# 8_ADC_chip.net
KiCad netlist of a schematic drawn in Altium Designer
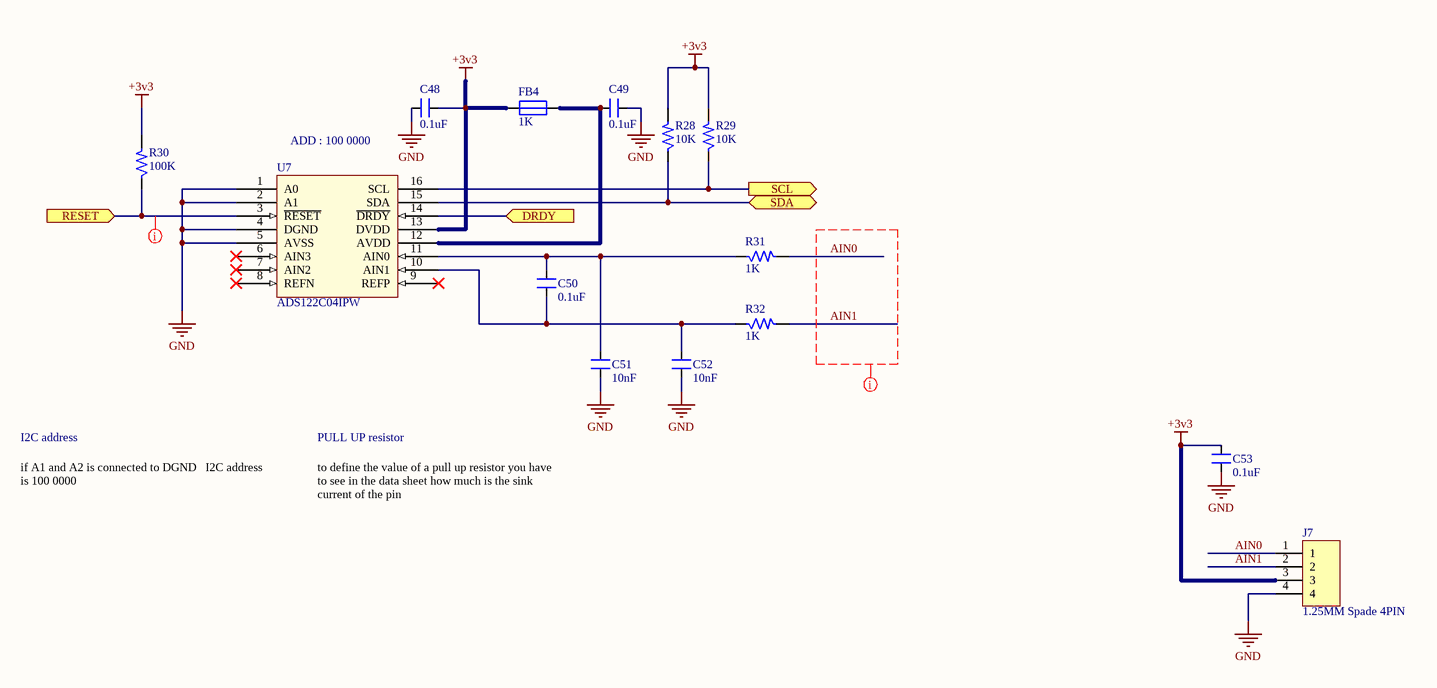
[diagram p0: [8]ADC_chip.SchDoc]

(export (version "E")
  (design (tool "Eeschema 10.0.6"))
  (components
    (comp (ref "C48")
      (value "0.1uF")
      (footprint "CAP_0805")
      (description "0.1µF ±5% 50V Ceramic Capacitor X7R 0805 (2012 Metric)")
      (fields
        (field (name "MANUFACTURER") "AVX Corporation")
        (field (name "MANUFACTURER PART NUMBER") "08055C104JAT4A")
      )
      (libsource (lib "ESTEEMPCBLIB") (part "CAP_0.1uF-50V-5%-0805"))
    )
    (comp (ref "C49")
      (value "0.1uF")
      (footprint "CAP_0805")
      (description "0.1µF ±5% 50V Ceramic Capacitor X7R 0805 (2012 Metric)")
      (fields
        (field (name "MANUFACTURER") "AVX Corporation")
        (field (name "MANUFACTURER PART NUMBER") "08055C104JAT4A")
      )
      (libsource (lib "ESTEEMPCBLIB") (part "CAP_0.1uF-50V-5%-0805"))
    )
    (comp (ref "C50")
      (value "0.1uF")
      (footprint "CAP_0805")
      (description "0.1µF ±5% 50V Ceramic Capacitor X7R 0805 (2012 Metric)")
      (fields
        (field (name "MANUFACTURER") "AVX Corporation")
        (field (name "MANUFACTURER PART NUMBER") "08055C104JAT4A")
      )
      (libsource (lib "ESTEEMPCBLIB") (part "CAP_0.1uF-50V-5%-0805"))
    )
    (comp (ref "C51")
      (value "10nF")
      (footprint "CAP_0805")
      (description "10000pF ±10% 50V Ceramic Capacitor X7R 0805 (2012 Metric)")
      (fields
        (field (name "MANUFACTURER") "Samsung")
        (field (name "MANUFACTURER PART NUMBER") "C0805C103K5RECAUTO")
      )
      (libsource (lib "ESTEEMPCBLIB") (part "CAP_10nF-50V-10%-0805"))
    )
    (comp (ref "C52")
      (value "10nF")
      (footprint "CAP_0805")
      (description "10000pF ±10% 50V Ceramic Capacitor X7R 0805 (2012 Metric)")
      (fields
        (field (name "MANUFACTURER") "Samsung")
        (field (name "MANUFACTURER PART NUMBER") "C0805C103K5RECAUTO")
      )
      (libsource (lib "ESTEEMPCBLIB") (part "CAP_10nF-50V-10%-0805"))
    )
    (comp (ref "C53")
      (value "0.1uF")
      (footprint "CAP_0805")
      (description "0.1µF ±5% 50V Ceramic Capacitor X7R 0805 (2012 Metric)")
      (fields
        (field (name "MANUFACTURER") "AVX Corporation")
        (field (name "MANUFACTURER PART NUMBER") "08055C104JAT4A")
      )
      (libsource (lib "ESTEEMPCBLIB") (part "CAP_0.1uF-50V-5%-0805"))
    )
    (comp (ref "FB4")
      (value "1K")
      (footprint "IND_0805")
      (description "1 kOhms @ 100MHz 1 Power Line Ferrite Bead 0805 (2012 Metric) 1.6A")
      (fields
        (field (name "MANUFACTURER") "Laird")
        (field (name "MANUFACTURER PART NUMBER") "BLM21SP102SH1D")
      )
      (libsource (lib "ESTEEMPCBLIB") (part "FB_1K-100MHZ-1.6A-0805"))
    )
    (comp (ref "J7")
      (value "1.25MM Spade 4PIN")
      (footprint "CON4_50_653004117322_TH_RA")
      (description "4 Pins, 1 Row 1.25mm Pitch, right angle Connector, male")
      (fields (field (name "MANUFACTURER PART NUMBER") "653004117322") (field (name "MANUFACTURER") "JST"))
      (libsource (lib "ESTEEMPCBLIB") (part "CON-PLG_4X1-50-RA-TH"))
    )
    (comp (ref "R28")
      (value "10K")
      (footprint "RES_0603")
      (description "10 kOhms ±1% 0.1W, 1/10W Chip Resistor 0603 (1608 Metric) Automotive AEC-Q200 Thick Film")
      (fields (field (name "MANUFACTURER") "Walsin") (field (name "MANUFACTURER PART NUMBER") "WR06X1002FTL"))
      (libsource (lib "ESTEEMPCBLIB") (part "RES_10K-0.1W-1%-0603"))
    )
    (comp (ref "R29")
      (value "10K")
      (footprint "RES_0603")
      (description "10 kOhms ±1% 0.1W, 1/10W Chip Resistor 0603 (1608 Metric) Automotive AEC-Q200 Thick Film")
      (fields (field (name "MANUFACTURER") "Walsin") (field (name "MANUFACTURER PART NUMBER") "WR06X1002FTL"))
      (libsource (lib "ESTEEMPCBLIB") (part "RES_10K-0.1W-1%-0603"))
    )
    (comp (ref "R30")
      (value "100K")
      (footprint "RES_0603")
      (description "100 kOhms ±1% 0.1W, 1/10W Chip Resistor 0603 (1608 Metric) Automotive AEC-Q200 Thick Film")
      (fields
        (field (name "MANUFACTURER") "Stackpole Electronics")
        (field (name "MANUFACTURER PART NUMBER") "RMCF0603FT100K")
      )
      (libsource (lib "ESTEEMPCBLIB") (part "RES_100K-0.1W-1%-0603"))
    )
    (comp (ref "R31")
      (value "1K")
      (footprint "RES_0603")
      (description "1 kOhms ±1% 0.1W, 1/10W Chip Resistor 0603 (1608 Metric) Automotive AEC-Q200 Thick Film")
      (fields (field (name "MANUFACTURER") "Walsin") (field (name "MANUFACTURER PART NUMBER") "WR06X1001FTL"))
      (libsource (lib "ESTEEMPCBLIB") (part "RES_1K-0.1W-1%-0603"))
    )
    (comp (ref "R32")
      (value "1K")
      (footprint "RES_0603")
      (description "1 kOhms ±1% 0.1W, 1/10W Chip Resistor 0603 (1608 Metric) Automotive AEC-Q200 Thick Film")
      (fields (field (name "MANUFACTURER") "Walsin") (field (name "MANUFACTURER PART NUMBER") "WR06X1001FTL"))
      (libsource (lib "ESTEEMPCBLIB") (part "RES_1K-0.1W-1%-0603"))
    )
    (comp (ref "U7")
      (value "ADS122C04IPW")
      (footprint "TSSOP16_25-59_294_54X14_SMT")
      (description "24 Bit Analog to Digital Converter 4 Input 1 Sigma-Delta 16-TSSOP")
      (fields (field (name "MANUFACTURER") "Texas Instruments"))
      (libsource (lib "ESTEEMPCBLIB") (part "IC_ADS122C04IPW"))
    )
  )
  (nets
    (net (code "1") (name "+3v3") (class "Default")
      (node (ref "C48") (pin "2") (pinfunction "2_2") (pintype "passive"))
      (node (ref "C53") (pin "2") (pinfunction "2_2") (pintype "passive"))
      (node (ref "FB4") (pin "1") (pinfunction "1_1") (pintype "passive"))
      (node (ref "J7") (pin "3") (pinfunction "3_3") (pintype "passive"))
      (node (ref "R28") (pin "2") (pinfunction "2_2") (pintype "passive"))
      (node (ref "R29") (pin "2") (pinfunction "2_2") (pintype "passive"))
      (node (ref "R30") (pin "2") (pinfunction "2_2") (pintype "passive"))
      (node (ref "U7") (pin "13") (pinfunction "DVDD_13") (pintype "power_in"))
    )
    (net (code "2") (name "/AIN0") (class "Default")
      (node (ref "J7") (pin "1") (pinfunction "1_1") (pintype "passive"))
      (node (ref "R31") (pin "2") (pinfunction "2_2") (pintype "passive"))
    )
    (net (code "3") (name "/AIN1") (class "Default")
      (node (ref "J7") (pin "2") (pinfunction "2_2") (pintype "passive"))
      (node (ref "R32") (pin "2") (pinfunction "2_2") (pintype "passive"))
    )
    (net (code "4") (name "/DRDY") (class "Default")
      (node (ref "U7") (pin "14") (pinfunction "DRDY_14") (pintype "input"))
    )
    (net (code "5") (name "/RESET") (class "Default")
      (node (ref "R30") (pin "1") (pinfunction "1_1") (pintype "passive"))
      (node (ref "U7") (pin "3") (pinfunction "RESET_3") (pintype "input"))
    )
    (net (code "6") (name "/SCL") (class "Default")
      (node (ref "R29") (pin "1") (pinfunction "1_1") (pintype "passive"))
      (node (ref "U7") (pin "16") (pinfunction "SCL_16") (pintype "open_collector"))
    )
    (net (code "7") (name "/SDA") (class "Default")
      (node (ref "R28") (pin "1") (pinfunction "1_1") (pintype "passive"))
      (node (ref "U7") (pin "15") (pinfunction "SDA_15") (pintype "open_collector"))
    )
    (net (code "8") (name "GND") (class "Default")
      (node (ref "C48") (pin "1") (pinfunction "1_1") (pintype "passive"))
      (node (ref "C49") (pin "2") (pinfunction "2_2") (pintype "passive"))
      (node (ref "C51") (pin "1") (pinfunction "1_1") (pintype "passive"))
      (node (ref "C52") (pin "1") (pinfunction "1_1") (pintype "passive"))
      (node (ref "C53") (pin "1") (pinfunction "1_1") (pintype "passive"))
      (node (ref "J7") (pin "4") (pinfunction "4_4") (pintype "passive"))
      (node (ref "U7") (pin "1") (pinfunction "A0_1") (pintype "passive"))
      (node (ref "U7") (pin "2") (pinfunction "A1_2") (pintype "passive"))
      (node (ref "U7") (pin "4") (pinfunction "DGND_4") (pintype "power_in"))
      (node (ref "U7") (pin "5") (pinfunction "AVSS_5") (pintype "power_in"))
    )
    (net (code "9") (name "Net-(U7-AIN0)") (class "Default")
      (node (ref "C50") (pin "2") (pinfunction "2_2") (pintype "passive"))
      (node (ref "C51") (pin "2") (pinfunction "2_2") (pintype "passive"))
      (node (ref "R31") (pin "1") (pinfunction "1_1") (pintype "passive"))
      (node (ref "U7") (pin "11") (pinfunction "AIN0_11") (pintype "input"))
    )
    (net (code "10") (name "Net-(U7-AIN1)") (class "Default")
      (node (ref "C50") (pin "1") (pinfunction "1_1") (pintype "passive"))
      (node (ref "C52") (pin "2") (pinfunction "2_2") (pintype "passive"))
      (node (ref "R32") (pin "1") (pinfunction "1_1") (pintype "passive"))
      (node (ref "U7") (pin "10") (pinfunction "AIN1_10") (pintype "input"))
    )
    (net (code "11") (name "Net-(U7-AVDD)") (class "Default")
      (node (ref "C49") (pin "1") (pinfunction "1_1") (pintype "passive"))
      (node (ref "FB4") (pin "2") (pinfunction "2_2") (pintype "passive"))
      (node (ref "U7") (pin "12") (pinfunction "AVDD_12") (pintype "power_in"))
    )
    (net (code "12") (name "unconnected-(U7-AIN2-Pad7)") (class "Default")
      (node (ref "U7") (pin "7") (pinfunction "AIN2_7") (pintype "input+no_connect"))
    )
    (net (code "13") (name "unconnected-(U7-AIN3-Pad6)") (class "Default")
      (node (ref "U7") (pin "6") (pinfunction "AIN3_6") (pintype "input+no_connect"))
    )
    (net (code "14") (name "unconnected-(U7-REFN-Pad8)") (class "Default")
      (node (ref "U7") (pin "8") (pinfunction "REFN_8") (pintype "input+no_connect"))
    )
    (net (code "15") (name "unconnected-(U7-REFP-Pad9)") (class "Default")
      (node (ref "U7") (pin "9") (pinfunction "REFP_9") (pintype "input+no_connect"))
    )
  )
)
